# 01_MCU.net
KiCad netlist of a schematic drawn in Altium Designer
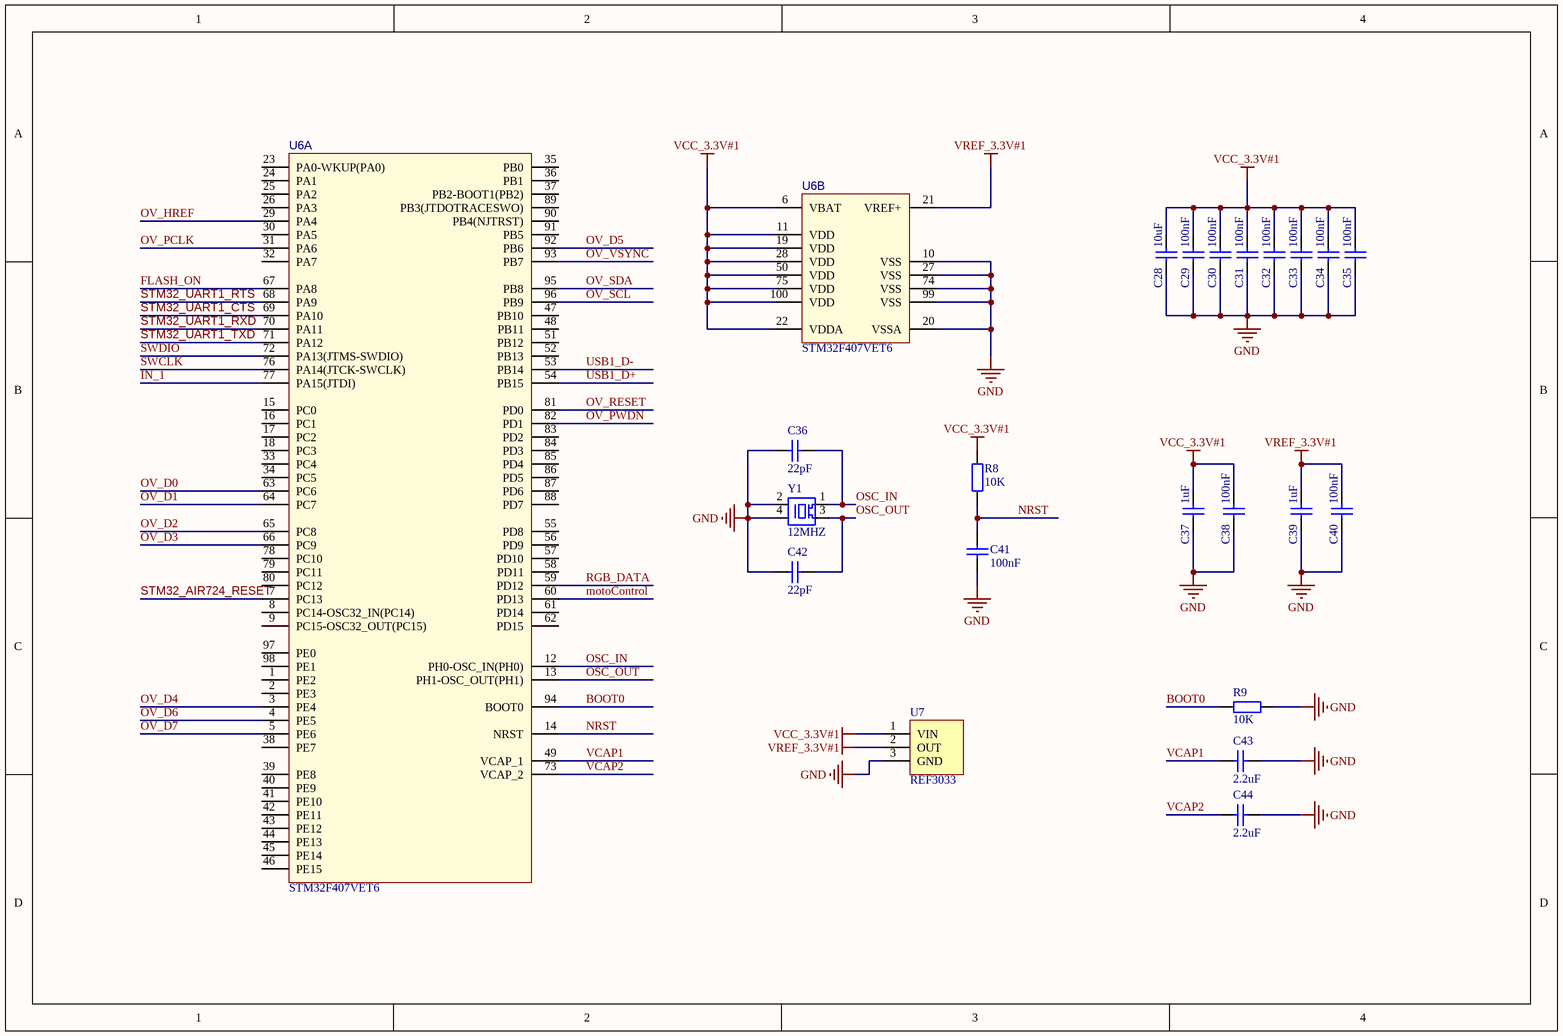
[diagram p0: 01_MCU.SchDoc]

(export (version "E")
  (design (tool "Eeschema 10.0.6"))
  (components
    (comp (ref "C28")
      (value "10uF")
      (footprint "0603-C")
      (description "贴片电容")
      (libsource (lib "封装库") (part "C"))
    )
    (comp (ref "C29")
      (value "100nF")
      (footprint "0603-C")
      (description "贴片电容")
      (libsource (lib "封装库") (part "C"))
    )
    (comp (ref "C30")
      (value "100nF")
      (footprint "0603-C")
      (description "贴片电容")
      (libsource (lib "封装库") (part "C"))
    )
    (comp (ref "C31")
      (value "100nF")
      (footprint "0603-C")
      (description "贴片电容")
      (libsource (lib "封装库") (part "C"))
    )
    (comp (ref "C32")
      (value "100nF")
      (footprint "0603-C")
      (description "贴片电容")
      (libsource (lib "封装库") (part "C"))
    )
    (comp (ref "C33")
      (value "100nF")
      (footprint "0603-C")
      (description "贴片电容")
      (libsource (lib "封装库") (part "C"))
    )
    (comp (ref "C34")
      (value "100nF")
      (footprint "0603-C")
      (description "贴片电容")
      (libsource (lib "封装库") (part "C"))
    )
    (comp (ref "C35")
      (value "100nF")
      (footprint "0603-C")
      (description "贴片电容")
      (libsource (lib "封装库") (part "C"))
    )
    (comp (ref "C36")
      (value "22pF")
      (footprint "0603-C")
      (description "贴片电容")
      (libsource (lib "封装库") (part "C"))
    )
    (comp (ref "C37")
      (value "1uF")
      (footprint "0603-C")
      (description "贴片电容")
      (libsource (lib "封装库") (part "C"))
    )
    (comp (ref "C38")
      (value "100nF")
      (footprint "0603-C")
      (description "贴片电容")
      (libsource (lib "封装库") (part "C"))
    )
    (comp (ref "C39")
      (value "1uF")
      (footprint "0603-C")
      (description "贴片电容")
      (libsource (lib "封装库") (part "C"))
    )
    (comp (ref "C40")
      (value "100nF")
      (footprint "0603-C")
      (description "贴片电容")
      (libsource (lib "封装库") (part "C"))
    )
    (comp (ref "C41")
      (value "100nF")
      (footprint "0603-C")
      (description "贴片电容")
      (libsource (lib "封装库") (part "C"))
    )
    (comp (ref "C42")
      (value "22pF")
      (footprint "0603-C")
      (description "贴片电容")
      (libsource (lib "封装库") (part "C"))
    )
    (comp (ref "C43")
      (value "2.2uF")
      (footprint "0603-C")
      (description "贴片电容")
      (libsource (lib "封装库") (part "C"))
    )
    (comp (ref "C44")
      (value "2.2uF")
      (footprint "0603-C")
      (description "贴片电容")
      (libsource (lib "封装库") (part "C"))
    )
    (comp (ref "R8")
      (value "10K")
      (footprint "0603-R")
      (description "贴片电阻")
      (libsource (lib "封装库") (part "R"))
    )
    (comp (ref "R9")
      (value "10K")
      (footprint "0603-R")
      (description "贴片电阻")
      (libsource (lib "封装库") (part "R"))
    )
    (comp (ref "U6")
      (value "STM32F407VET6")
      (footprint "STM32F407VET6")
      (fields (field (name "MANUFACTURER") "ST(意法半导体)"))
      (libsource (lib "封装库") (part "STM32F407VET6"))
    )
    (comp (ref "U7") (value "REF3033") (footprint "REF3033") (libsource (lib "封装库") (part "REF3033")))
    (comp (ref "Y1")
      (value "12MHZ")
      (footprint "3225")
      (description "无源晶振")
      (libsource (lib "数传模块") (part "Y"))
    )
  )
  (nets
    (net (code "1") (name "/BOOT0") (class "Default")
      (node (ref "R9") (pin "2") (pinfunction "2_2") (pintype "passive"))
      (node (ref "U6") (pin "94") (pinfunction "BOOT0_94") (pintype "passive"))
    )
    (net (code "2") (name "/FLASH_ON") (class "Default")
      (node (ref "U6") (pin "67") (pinfunction "PA8_67") (pintype "passive"))
    )
    (net (code "3") (name "/IN_1") (class "Default")
      (node (ref "U6") (pin "77") (pinfunction "PA15(JTDI)_77") (pintype "passive"))
    )
    (net (code "4") (name "/NRST") (class "Default")
      (node (ref "C41") (pin "2") (pinfunction "2_2") (pintype "passive"))
      (node (ref "R8") (pin "1") (pinfunction "1_1") (pintype "passive"))
      (node (ref "U6") (pin "14") (pinfunction "NRST_14") (pintype "passive"))
    )
    (net (code "5") (name "/OSC_IN") (class "Default")
      (node (ref "C36") (pin "2") (pinfunction "2_2") (pintype "passive"))
      (node (ref "U6") (pin "12") (pinfunction "PH0-OSC_IN(PH0)_12") (pintype "passive"))
      (node (ref "Y1") (pin "1") (pinfunction "XTAL1_1") (pintype "passive"))
    )
    (net (code "6") (name "/OSC_OUT") (class "Default")
      (node (ref "C42") (pin "2") (pinfunction "2_2") (pintype "passive"))
      (node (ref "U6") (pin "13") (pinfunction "PH1-OSC_OUT(PH1)_13") (pintype "passive"))
      (node (ref "Y1") (pin "3") (pinfunction "XTAL3_3") (pintype "passive"))
    )
    (net (code "7") (name "/OV_D0") (class "Default")
      (node (ref "U6") (pin "63") (pinfunction "PC6_63") (pintype "passive"))
    )
    (net (code "8") (name "/OV_D1") (class "Default")
      (node (ref "U6") (pin "64") (pinfunction "PC7_64") (pintype "passive"))
    )
    (net (code "9") (name "/OV_D2") (class "Default")
      (node (ref "U6") (pin "65") (pinfunction "PC8_65") (pintype "passive"))
    )
    (net (code "10") (name "/OV_D3") (class "Default")
      (node (ref "U6") (pin "66") (pinfunction "PC9_66") (pintype "passive"))
    )
    (net (code "11") (name "/OV_D4") (class "Default")
      (node (ref "U6") (pin "3") (pinfunction "PE4_3") (pintype "passive"))
    )
    (net (code "12") (name "/OV_D5") (class "Default")
      (node (ref "U6") (pin "92") (pinfunction "PB6_92") (pintype "passive"))
    )
    (net (code "13") (name "/OV_D6") (class "Default")
      (node (ref "U6") (pin "4") (pinfunction "PE5_4") (pintype "passive"))
    )
    (net (code "14") (name "/OV_D7") (class "Default")
      (node (ref "U6") (pin "5") (pinfunction "PE6_5") (pintype "passive"))
    )
    (net (code "15") (name "/OV_HREF") (class "Default")
      (node (ref "U6") (pin "29") (pinfunction "PA4_29") (pintype "passive"))
    )
    (net (code "16") (name "/OV_PCLK") (class "Default")
      (node (ref "U6") (pin "31") (pinfunction "PA6_31") (pintype "passive"))
    )
    (net (code "17") (name "/OV_PWDN") (class "Default")
      (node (ref "U6") (pin "82") (pinfunction "PD1_82") (pintype "passive"))
    )
    (net (code "18") (name "/OV_RESET") (class "Default")
      (node (ref "U6") (pin "81") (pinfunction "PD0_81") (pintype "passive"))
    )
    (net (code "19") (name "/OV_SCL") (class "Default")
      (node (ref "U6") (pin "96") (pinfunction "PB9_96") (pintype "passive"))
    )
    (net (code "20") (name "/OV_SDA") (class "Default")
      (node (ref "U6") (pin "95") (pinfunction "PB8_95") (pintype "passive"))
    )
    (net (code "21") (name "/OV_VSYNC") (class "Default")
      (node (ref "U6") (pin "93") (pinfunction "PB7_93") (pintype "passive"))
    )
    (net (code "22") (name "/RGB_DATA") (class "Default")
      (node (ref "U6") (pin "59") (pinfunction "PD12_59") (pintype "passive"))
    )
    (net (code "23") (name "/STM32_AIR724_RESET") (class "Default")
      (node (ref "U6") (pin "7") (pinfunction "PC13_7") (pintype "passive"))
    )
    (net (code "24") (name "/STM32_UART1_CTS") (class "Default")
      (node (ref "U6") (pin "69") (pinfunction "PA10_69") (pintype "passive"))
    )
    (net (code "25") (name "/STM32_UART1_RTS") (class "Default")
      (node (ref "U6") (pin "68") (pinfunction "PA9_68") (pintype "passive"))
    )
    (net (code "26") (name "/STM32_UART1_RXD") (class "Default")
      (node (ref "U6") (pin "70") (pinfunction "PA11_70") (pintype "passive"))
    )
    (net (code "27") (name "/STM32_UART1_TXD") (class "Default")
      (node (ref "U6") (pin "71") (pinfunction "PA12_71") (pintype "passive"))
    )
    (net (code "28") (name "/SWCLK") (class "Default")
      (node (ref "U6") (pin "76") (pinfunction "PA14(JTCK-SWCLK)_76") (pintype "passive"))
    )
    (net (code "29") (name "/SWDIO") (class "Default")
      (node (ref "U6") (pin "72") (pinfunction "PA13(JTMS-SWDIO)_72") (pintype "passive"))
    )
    (net (code "30") (name "/USB1_D+") (class "Default")
      (node (ref "U6") (pin "54") (pinfunction "PB15_54") (pintype "passive"))
    )
    (net (code "31") (name "/USB1_D-") (class "Default")
      (node (ref "U6") (pin "53") (pinfunction "PB14_53") (pintype "passive"))
    )
    (net (code "32") (name "/VCAP1") (class "Default")
      (node (ref "C43") (pin "1") (pinfunction "1_1") (pintype "passive"))
      (node (ref "U6") (pin "49") (pinfunction "VCAP_1_49") (pintype "passive"))
    )
    (net (code "33") (name "/VCAP2") (class "Default")
      (node (ref "C44") (pin "1") (pinfunction "1_1") (pintype "passive"))
      (node (ref "U6") (pin "73") (pinfunction "VCAP_2_73") (pintype "passive"))
    )
    (net (code "34") (name "/motoControl") (class "Default")
      (node (ref "U6") (pin "60") (pinfunction "PD13_60") (pintype "passive"))
    )
    (net (code "35") (name "GND") (class "Default")
      (node (ref "C28") (pin "1") (pinfunction "1_1") (pintype "passive"))
      (node (ref "C29") (pin "1") (pinfunction "1_1") (pintype "passive"))
      (node (ref "C30") (pin "1") (pinfunction "1_1") (pintype "passive"))
      (node (ref "C31") (pin "1") (pinfunction "1_1") (pintype "passive"))
      (node (ref "C32") (pin "1") (pinfunction "1_1") (pintype "passive"))
      (node (ref "C33") (pin "1") (pinfunction "1_1") (pintype "passive"))
      (node (ref "C34") (pin "1") (pinfunction "1_1") (pintype "passive"))
      (node (ref "C35") (pin "1") (pinfunction "1_1") (pintype "passive"))
      (node (ref "C36") (pin "1") (pinfunction "1_1") (pintype "passive"))
      (node (ref "C37") (pin "1") (pinfunction "1_1") (pintype "passive"))
      (node (ref "C38") (pin "1") (pinfunction "1_1") (pintype "passive"))
      (node (ref "C39") (pin "1") (pinfunction "1_1") (pintype "passive"))
      (node (ref "C40") (pin "1") (pinfunction "1_1") (pintype "passive"))
      (node (ref "C41") (pin "1") (pinfunction "1_1") (pintype "passive"))
      (node (ref "C42") (pin "1") (pinfunction "1_1") (pintype "passive"))
      (node (ref "C43") (pin "2") (pinfunction "2_2") (pintype "passive"))
      (node (ref "C44") (pin "2") (pinfunction "2_2") (pintype "passive"))
      (node (ref "R9") (pin "1") (pinfunction "1_1") (pintype "passive"))
      (node (ref "U6") (pin "10") (pinfunction "VSS_10") (pintype "passive"))
      (node (ref "U6") (pin "20") (pinfunction "VSSA_20") (pintype "passive"))
      (node (ref "U6") (pin "27") (pinfunction "VSS_27") (pintype "passive"))
      (node (ref "U6") (pin "74") (pinfunction "VSS_74") (pintype "passive"))
      (node (ref "U6") (pin "99") (pinfunction "VSS_99") (pintype "passive"))
      (node (ref "U7") (pin "3") (pinfunction "GND_3") (pintype "passive"))
      (node (ref "Y1") (pin "2") (pinfunction "GND_2") (pintype "passive"))
      (node (ref "Y1") (pin "4") (pinfunction "GND_4") (pintype "passive"))
    )
    (net (code "36") (name "VCC_3.3V#1") (class "Default")
      (node (ref "C28") (pin "2") (pinfunction "2_2") (pintype "passive"))
      (node (ref "C29") (pin "2") (pinfunction "2_2") (pintype "passive"))
      (node (ref "C30") (pin "2") (pinfunction "2_2") (pintype "passive"))
      (node (ref "C31") (pin "2") (pinfunction "2_2") (pintype "passive"))
      (node (ref "C32") (pin "2") (pinfunction "2_2") (pintype "passive"))
      (node (ref "C33") (pin "2") (pinfunction "2_2") (pintype "passive"))
      (node (ref "C34") (pin "2") (pinfunction "2_2") (pintype "passive"))
      (node (ref "C35") (pin "2") (pinfunction "2_2") (pintype "passive"))
      (node (ref "C37") (pin "2") (pinfunction "2_2") (pintype "passive"))
      (node (ref "C38") (pin "2") (pinfunction "2_2") (pintype "passive"))
      (node (ref "R8") (pin "2") (pinfunction "2_2") (pintype "passive"))
      (node (ref "U6") (pin "100") (pinfunction "VDD_100") (pintype "passive"))
      (node (ref "U6") (pin "11") (pinfunction "VDD_11") (pintype "passive"))
      (node (ref "U6") (pin "19") (pinfunction "VDD_19") (pintype "passive"))
      (node (ref "U6") (pin "22") (pinfunction "VDDA_22") (pintype "passive"))
      (node (ref "U6") (pin "28") (pinfunction "VDD_28") (pintype "passive"))
      (node (ref "U6") (pin "50") (pinfunction "VDD_50") (pintype "passive"))
      (node (ref "U6") (pin "6") (pinfunction "VBAT_6") (pintype "passive"))
      (node (ref "U6") (pin "75") (pinfunction "VDD_75") (pintype "passive"))
      (node (ref "U7") (pin "1") (pinfunction "VIN_1") (pintype "passive"))
    )
    (net (code "37") (name "VREF_3.3V#1") (class "Default")
      (node (ref "C39") (pin "2") (pinfunction "2_2") (pintype "passive"))
      (node (ref "C40") (pin "2") (pinfunction "2_2") (pintype "passive"))
      (node (ref "U6") (pin "21") (pinfunction "VREF+_21") (pintype "passive"))
      (node (ref "U7") (pin "2") (pinfunction "OUT_2") (pintype "passive"))
    )
    (net (code "38") (name "unconnected-(U6A-PA0-WKUP(PA0)-Pad23)") (class "Default")
      (node (ref "U6") (pin "23") (pinfunction "PA0-WKUP(PA0)_23") (pintype "passive"))
    )
    (net (code "39") (name "unconnected-(U6A-PA1-Pad24)") (class "Default")
      (node (ref "U6") (pin "24") (pinfunction "PA1_24") (pintype "passive"))
    )
    (net (code "40") (name "unconnected-(U6A-PA2-Pad25)") (class "Default")
      (node (ref "U6") (pin "25") (pinfunction "PA2_25") (pintype "passive"))
    )
    (net (code "41") (name "unconnected-(U6A-PA3-Pad26)") (class "Default")
      (node (ref "U6") (pin "26") (pinfunction "PA3_26") (pintype "passive"))
    )
    (net (code "42") (name "unconnected-(U6A-PA5-Pad30)") (class "Default")
      (node (ref "U6") (pin "30") (pinfunction "PA5_30") (pintype "passive"))
    )
    (net (code "43") (name "unconnected-(U6A-PA7-Pad32)") (class "Default")
      (node (ref "U6") (pin "32") (pinfunction "PA7_32") (pintype "passive"))
    )
    (net (code "44") (name "unconnected-(U6A-PB0-Pad35)") (class "Default")
      (node (ref "U6") (pin "35") (pinfunction "PB0_35") (pintype "passive"))
    )
    (net (code "45") (name "unconnected-(U6A-PB1-Pad36)") (class "Default")
      (node (ref "U6") (pin "36") (pinfunction "PB1_36") (pintype "passive"))
    )
    (net (code "46") (name "unconnected-(U6A-PB2-BOOT1(PB2)-Pad37)") (class "Default")
      (node (ref "U6") (pin "37") (pinfunction "PB2-BOOT1(PB2)_37") (pintype "passive"))
    )
    (net (code "47") (name "unconnected-(U6A-PB3(JTDOTRACESWO)-Pad89)") (class "Default")
      (node (ref "U6") (pin "89") (pinfunction "PB3(JTDOTRACESWO)_89") (pintype "passive"))
    )
    (net (code "48") (name "unconnected-(U6A-PB4(NJTRST)-Pad90)") (class "Default")
      (node (ref "U6") (pin "90") (pinfunction "PB4(NJTRST)_90") (pintype "passive"))
    )
    (net (code "49") (name "unconnected-(U6A-PB5-Pad91)") (class "Default")
      (node (ref "U6") (pin "91") (pinfunction "PB5_91") (pintype "passive"))
    )
    (net (code "50") (name "unconnected-(U6A-PB10-Pad47)") (class "Default")
      (node (ref "U6") (pin "47") (pinfunction "PB10_47") (pintype "passive"))
    )
    (net (code "51") (name "unconnected-(U6A-PB11-Pad48)") (class "Default")
      (node (ref "U6") (pin "48") (pinfunction "PB11_48") (pintype "passive"))
    )
    (net (code "52") (name "unconnected-(U6A-PB12-Pad51)") (class "Default")
      (node (ref "U6") (pin "51") (pinfunction "PB12_51") (pintype "passive"))
    )
    (net (code "53") (name "unconnected-(U6A-PB13-Pad52)") (class "Default")
      (node (ref "U6") (pin "52") (pinfunction "PB13_52") (pintype "passive"))
    )
    (net (code "54") (name "unconnected-(U6A-PC0-Pad15)") (class "Default")
      (node (ref "U6") (pin "15") (pinfunction "PC0_15") (pintype "passive"))
    )
    (net (code "55") (name "unconnected-(U6A-PC1-Pad16)") (class "Default")
      (node (ref "U6") (pin "16") (pinfunction "PC1_16") (pintype "passive"))
    )
    (net (code "56") (name "unconnected-(U6A-PC2-Pad17)") (class "Default")
      (node (ref "U6") (pin "17") (pinfunction "PC2_17") (pintype "passive"))
    )
    (net (code "57") (name "unconnected-(U6A-PC3-Pad18)") (class "Default")
      (node (ref "U6") (pin "18") (pinfunction "PC3_18") (pintype "passive"))
    )
    (net (code "58") (name "unconnected-(U6A-PC4-Pad33)") (class "Default")
      (node (ref "U6") (pin "33") (pinfunction "PC4_33") (pintype "passive"))
    )
    (net (code "59") (name "unconnected-(U6A-PC5-Pad34)") (class "Default")
      (node (ref "U6") (pin "34") (pinfunction "PC5_34") (pintype "passive"))
    )
    (net (code "60") (name "unconnected-(U6A-PC10-Pad78)") (class "Default")
      (node (ref "U6") (pin "78") (pinfunction "PC10_78") (pintype "passive"))
    )
    (net (code "61") (name "unconnected-(U6A-PC11-Pad79)") (class "Default")
      (node (ref "U6") (pin "79") (pinfunction "PC11_79") (pintype "passive"))
    )
    (net (code "62") (name "unconnected-(U6A-PC12-Pad80)") (class "Default")
      (node (ref "U6") (pin "80") (pinfunction "PC12_80") (pintype "passive"))
    )
    (net (code "63") (name "unconnected-(U6A-PC14-OSC32_IN(PC14)-Pad8)") (class "Default")
      (node (ref "U6") (pin "8") (pinfunction "PC14-OSC32_IN(PC14)_8") (pintype "passive"))
    )
    (net (code "64") (name "unconnected-(U6A-PC15-OSC32_OUT(PC15)-Pad9)") (class "Default")
      (node (ref "U6") (pin "9") (pinfunction "PC15-OSC32_OUT(PC15)_9") (pintype "passive"))
    )
    (net (code "65") (name "unconnected-(U6A-PD2-Pad83)") (class "Default")
      (node (ref "U6") (pin "83") (pinfunction "PD2_83") (pintype "passive"))
    )
    (net (code "66") (name "unconnected-(U6A-PD3-Pad84)") (class "Default")
      (node (ref "U6") (pin "84") (pinfunction "PD3_84") (pintype "passive"))
    )
    (net (code "67") (name "unconnected-(U6A-PD4-Pad85)") (class "Default")
      (node (ref "U6") (pin "85") (pinfunction "PD4_85") (pintype "passive"))
    )
    (net (code "68") (name "unconnected-(U6A-PD5-Pad86)") (class "Default")
      (node (ref "U6") (pin "86") (pinfunction "PD5_86") (pintype "passive"))
    )
    (net (code "69") (name "unconnected-(U6A-PD6-Pad87)") (class "Default")
      (node (ref "U6") (pin "87") (pinfunction "PD6_87") (pintype "passive"))
    )
    (net (code "70") (name "unconnected-(U6A-PD7-Pad88)") (class "Default")
      (node (ref "U6") (pin "88") (pinfunction "PD7_88") (pintype "passive"))
    )
    (net (code "71") (name "unconnected-(U6A-PD8-Pad55)") (class "Default")
      (node (ref "U6") (pin "55") (pinfunction "PD8_55") (pintype "passive"))
    )
    (net (code "72") (name "unconnected-(U6A-PD9-Pad56)") (class "Default")
      (node (ref "U6") (pin "56") (pinfunction "PD9_56") (pintype "passive"))
    )
    (net (code "73") (name "unconnected-(U6A-PD10-Pad57)") (class "Default")
      (node (ref "U6") (pin "57") (pinfunction "PD10_57") (pintype "passive"))
    )
    (net (code "74") (name "unconnected-(U6A-PD11-Pad58)") (class "Default")
      (node (ref "U6") (pin "58") (pinfunction "PD11_58") (pintype "passive"))
    )
    (net (code "75") (name "unconnected-(U6A-PD14-Pad61)") (class "Default")
      (node (ref "U6") (pin "61") (pinfunction "PD14_61") (pintype "passive"))
    )
    (net (code "76") (name "unconnected-(U6A-PD15-Pad62)") (class "Default")
      (node (ref "U6") (pin "62") (pinfunction "PD15_62") (pintype "passive"))
    )
    (net (code "77") (name "unconnected-(U6A-PE0-Pad97)") (class "Default")
      (node (ref "U6") (pin "97") (pinfunction "PE0_97") (pintype "passive"))
    )
    (net (code "78") (name "unconnected-(U6A-PE1-Pad98)") (class "Default")
      (node (ref "U6") (pin "98") (pinfunction "PE1_98") (pintype "passive"))
    )
    (net (code "79") (name "unconnected-(U6A-PE2-Pad1)") (class "Default")
      (node (ref "U6") (pin "1") (pinfunction "PE2_1") (pintype "passive"))
    )
    (net (code "80") (name "unconnected-(U6A-PE3-Pad2)") (class "Default")
      (node (ref "U6") (pin "2") (pinfunction "PE3_2") (pintype "passive"))
    )
    (net (code "81") (name "unconnected-(U6A-PE7-Pad38)") (class "Default")
      (node (ref "U6") (pin "38") (pinfunction "PE7_38") (pintype "passive"))
    )
    (net (code "82") (name "unconnected-(U6A-PE8-Pad39)") (class "Default")
      (node (ref "U6") (pin "39") (pinfunction "PE8_39") (pintype "passive"))
    )
    (net (code "83") (name "unconnected-(U6A-PE9-Pad40)") (class "Default")
      (node (ref "U6") (pin "40") (pinfunction "PE9_40") (pintype "passive"))
    )
    (net (code "84") (name "unconnected-(U6A-PE10-Pad41)") (class "Default")
      (node (ref "U6") (pin "41") (pinfunction "PE10_41") (pintype "passive"))
    )
    (net (code "85") (name "unconnected-(U6A-PE11-Pad42)") (class "Default")
      (node (ref "U6") (pin "42") (pinfunction "PE11_42") (pintype "passive"))
    )
    (net (code "86") (name "unconnected-(U6A-PE12-Pad43)") (class "Default")
      (node (ref "U6") (pin "43") (pinfunction "PE12_43") (pintype "passive"))
    )
    (net (code "87") (name "unconnected-(U6A-PE13-Pad44)") (class "Default")
      (node (ref "U6") (pin "44") (pinfunction "PE13_44") (pintype "passive"))
    )
    (net (code "88") (name "unconnected-(U6A-PE14-Pad45)") (class "Default")
      (node (ref "U6") (pin "45") (pinfunction "PE14_45") (pintype "passive"))
    )
    (net (code "89") (name "unconnected-(U6A-PE15-Pad46)") (class "Default")
      (node (ref "U6") (pin "46") (pinfunction "PE15_46") (pintype "passive"))
    )
  )
)
